# Placa_frizzy.net
KiCad netlist of a schematic drawn in EAGLE
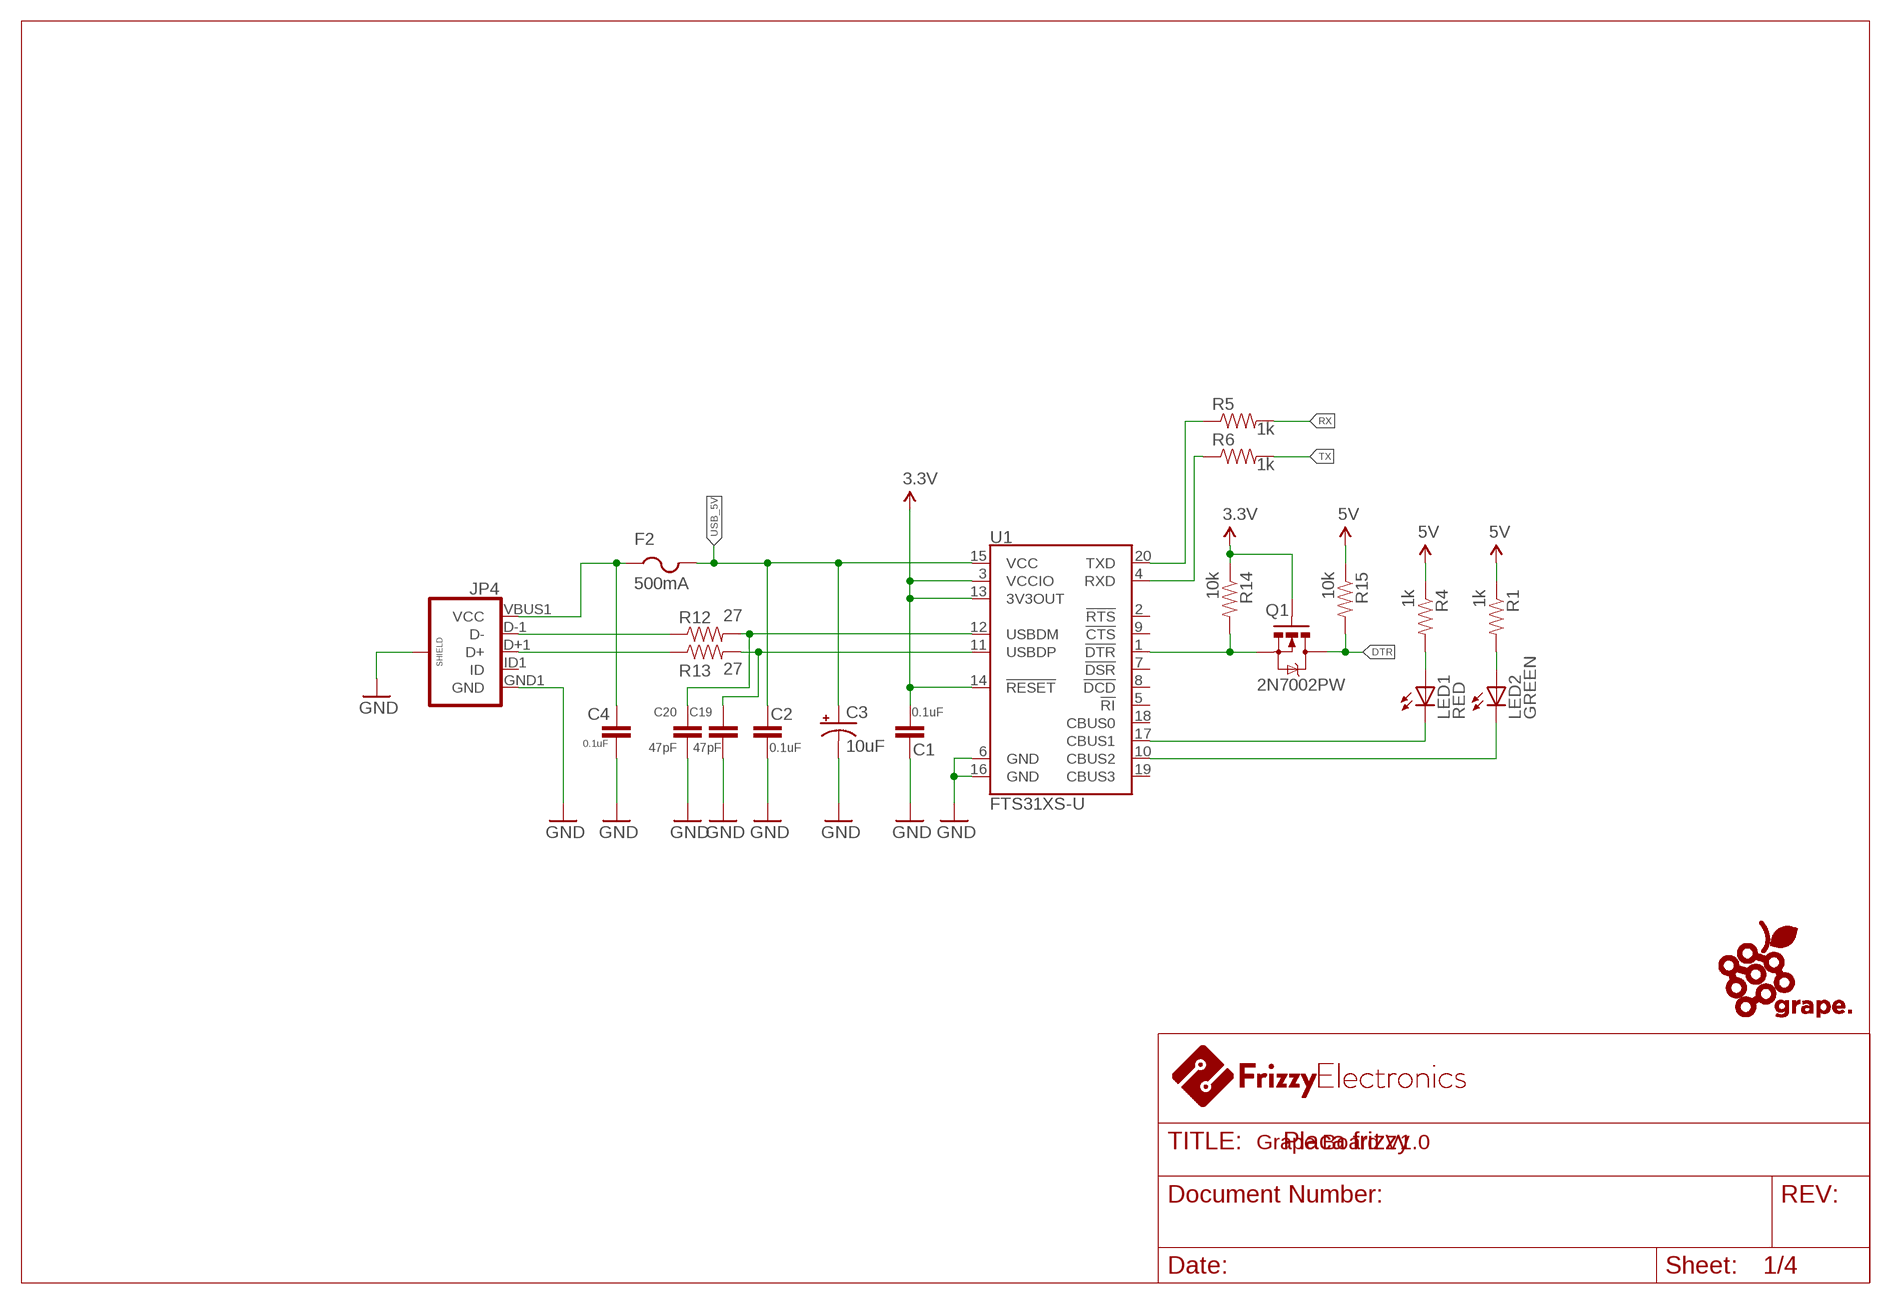
[diagram p0: schematic, sheet 1]
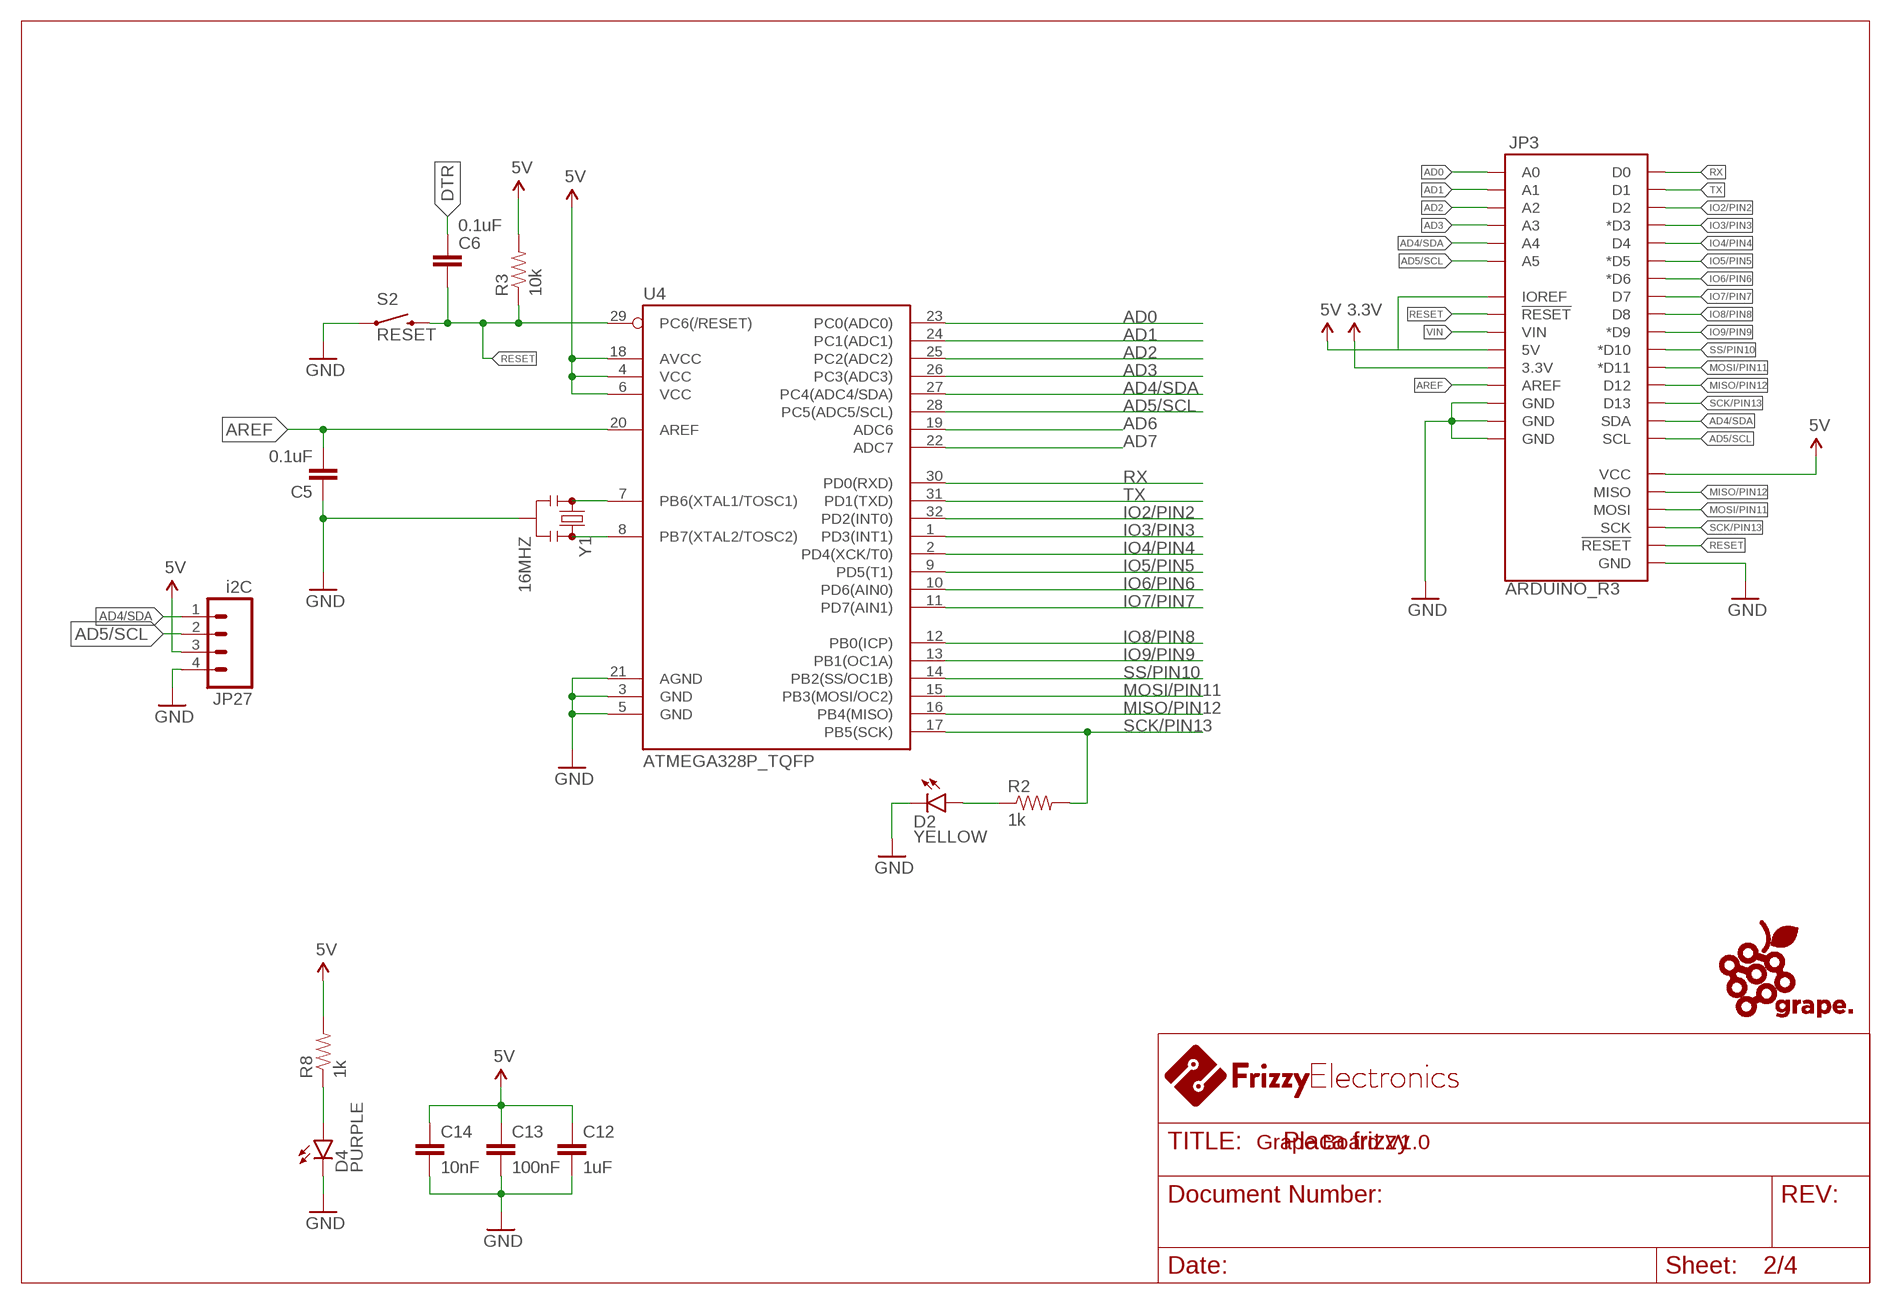
[diagram p1: schematic, sheet 2]
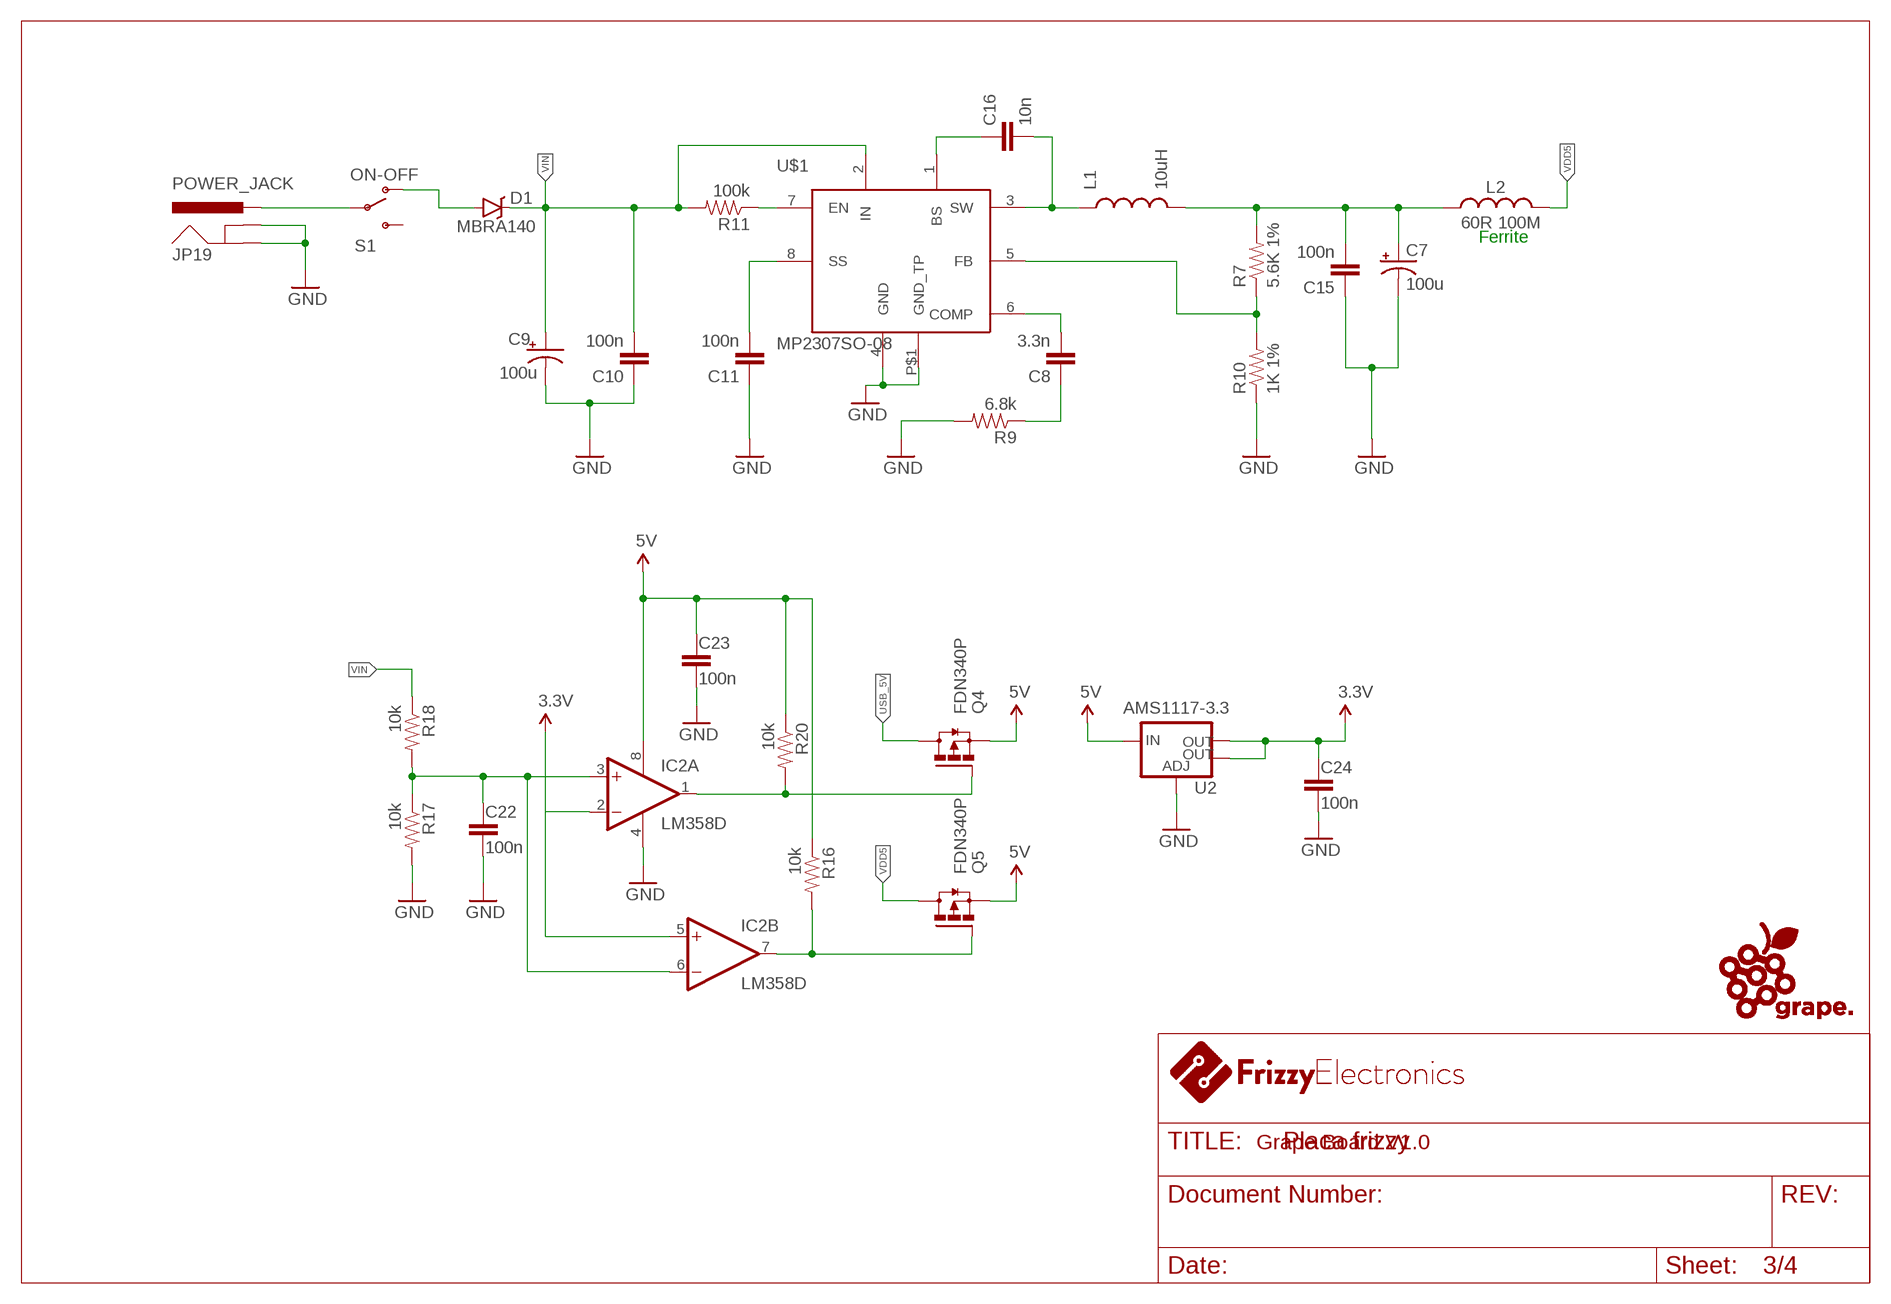
[diagram p2: schematic, sheet 3]
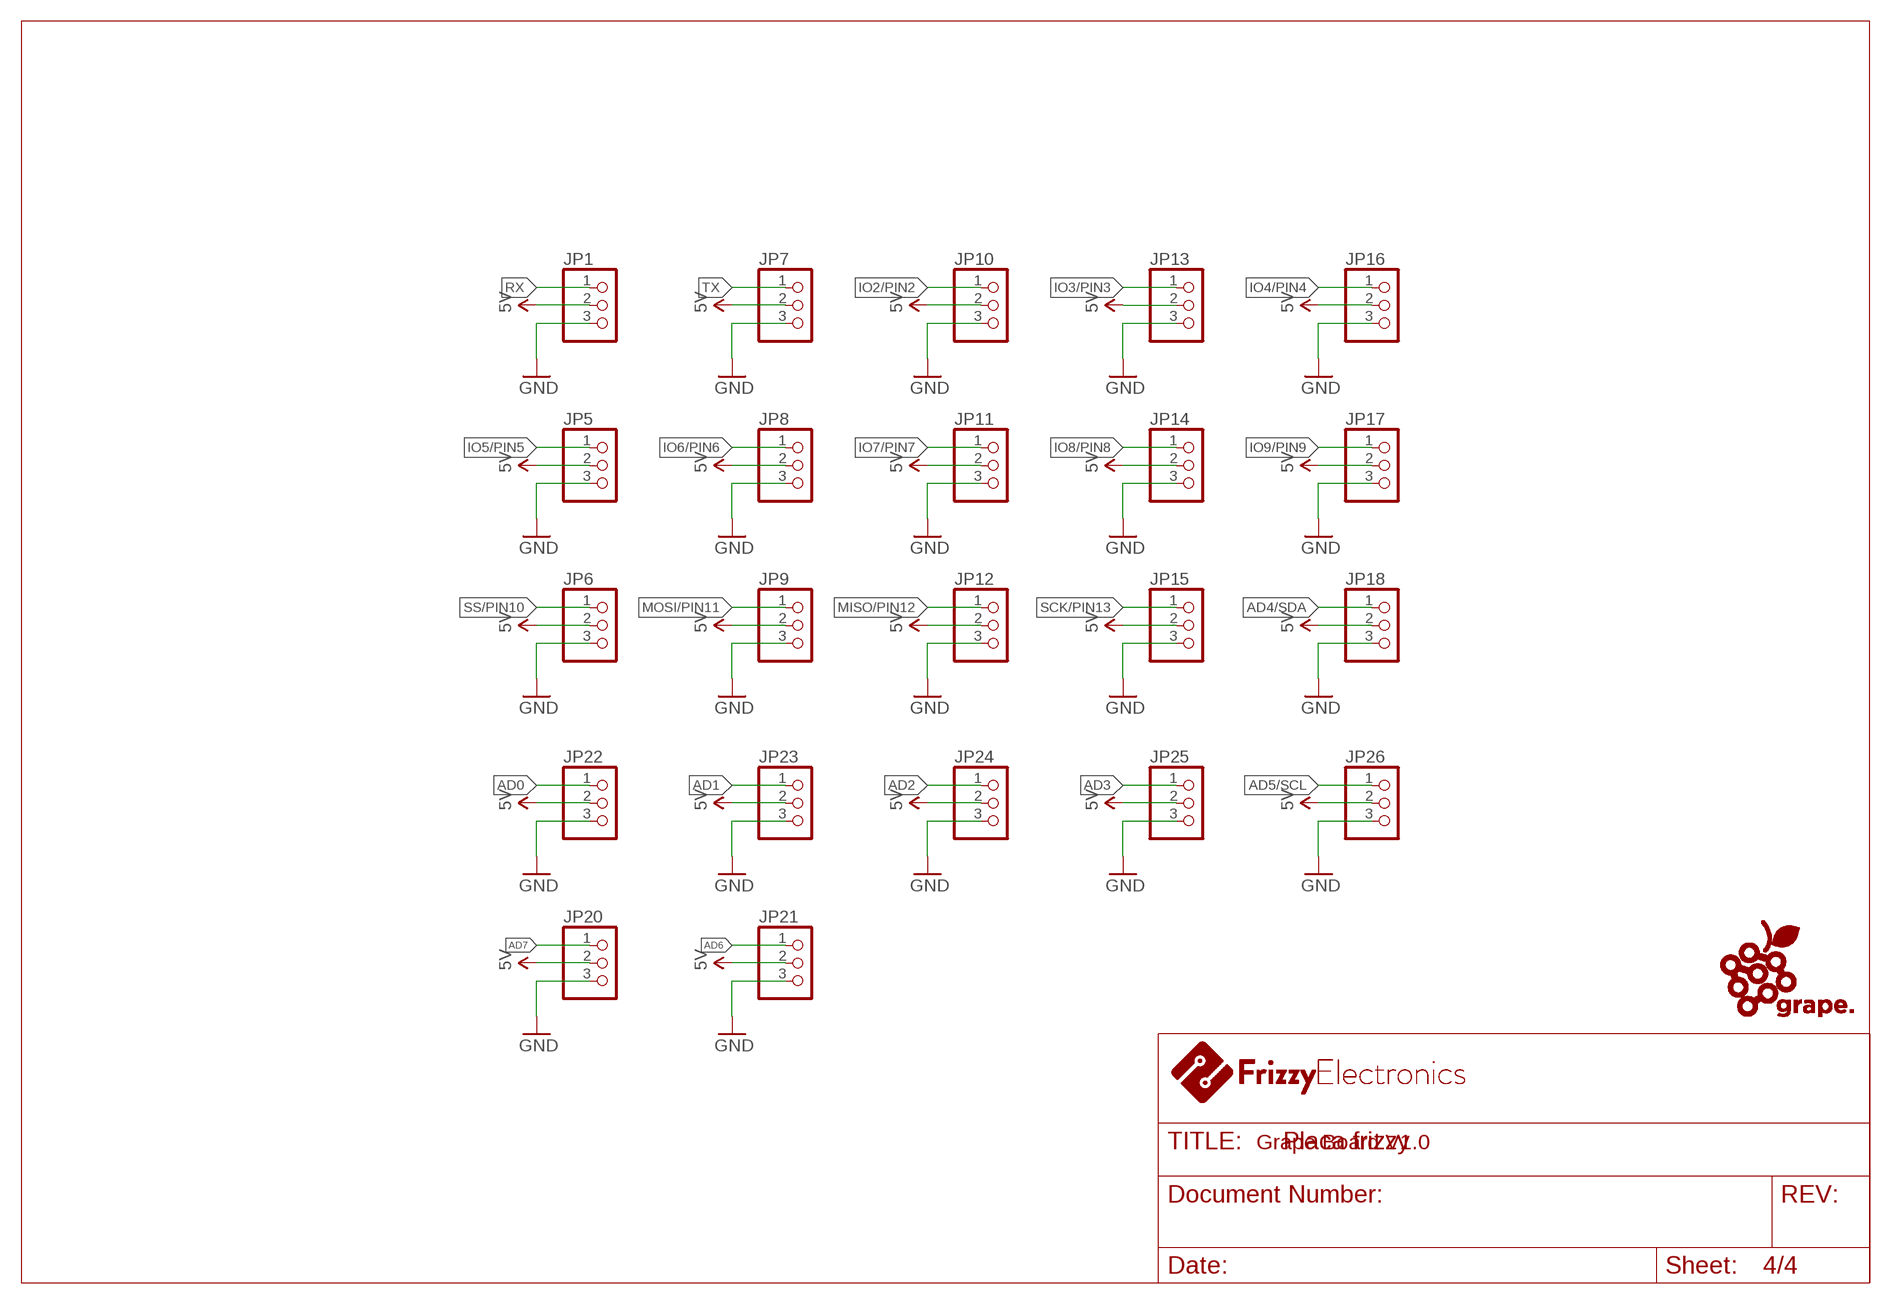
[diagram p3: schematic, sheet 4]

(export (version "E")
  (design (tool "Eeschema 10.0.6"))
  (components
    (comp (ref "JP1")
      (value "PINHD-1X3")
      (footprint "eagle-import:1X03")
      (libsource (lib "eagle-import") (part "PINHD-1X3"))
    )
    (comp (ref "JP5")
      (value "PINHD-1X3")
      (footprint "eagle-import:1X03")
      (libsource (lib "eagle-import") (part "PINHD-1X3"))
    )
    (comp (ref "JP6")
      (value "PINHD-1X3")
      (footprint "eagle-import:1X03")
      (libsource (lib "eagle-import") (part "PINHD-1X3"))
    )
    (comp (ref "JP7")
      (value "PINHD-1X3")
      (footprint "eagle-import:1X03")
      (libsource (lib "eagle-import") (part "PINHD-1X3"))
    )
    (comp (ref "JP8")
      (value "PINHD-1X3")
      (footprint "eagle-import:1X03")
      (libsource (lib "eagle-import") (part "PINHD-1X3"))
    )
    (comp (ref "JP9")
      (value "PINHD-1X3")
      (footprint "eagle-import:1X03")
      (libsource (lib "eagle-import") (part "PINHD-1X3"))
    )
    (comp (ref "JP10")
      (value "PINHD-1X3")
      (footprint "eagle-import:1X03")
      (libsource (lib "eagle-import") (part "PINHD-1X3"))
    )
    (comp (ref "JP11")
      (value "PINHD-1X3")
      (footprint "eagle-import:1X03")
      (libsource (lib "eagle-import") (part "PINHD-1X3"))
    )
    (comp (ref "JP12")
      (value "PINHD-1X3")
      (footprint "eagle-import:1X03")
      (libsource (lib "eagle-import") (part "PINHD-1X3"))
    )
    (comp (ref "JP13")
      (value "PINHD-1X3")
      (footprint "eagle-import:1X03")
      (libsource (lib "eagle-import") (part "PINHD-1X3"))
    )
    (comp (ref "JP14")
      (value "PINHD-1X3")
      (footprint "eagle-import:1X03")
      (libsource (lib "eagle-import") (part "PINHD-1X3"))
    )
    (comp (ref "JP15")
      (value "PINHD-1X3")
      (footprint "eagle-import:1X03")
      (libsource (lib "eagle-import") (part "PINHD-1X3"))
    )
    (comp (ref "JP16")
      (value "PINHD-1X3")
      (footprint "eagle-import:1X03")
      (libsource (lib "eagle-import") (part "PINHD-1X3"))
    )
    (comp (ref "JP17")
      (value "PINHD-1X3")
      (footprint "eagle-import:1X03")
      (libsource (lib "eagle-import") (part "PINHD-1X3"))
    )
    (comp (ref "JP18")
      (value "PINHD-1X3")
      (footprint "eagle-import:1X03")
      (libsource (lib "eagle-import") (part "PINHD-1X3"))
    )
    (comp (ref "JP20")
      (value "PINHD-1X3")
      (footprint "eagle-import:1X03")
      (libsource (lib "eagle-import") (part "PINHD-1X3"))
    )
    (comp (ref "JP21")
      (value "PINHD-1X3")
      (footprint "eagle-import:1X03")
      (libsource (lib "eagle-import") (part "PINHD-1X3"))
    )
    (comp (ref "JP22")
      (value "PINHD-1X3")
      (footprint "eagle-import:1X03")
      (libsource (lib "eagle-import") (part "PINHD-1X3"))
    )
    (comp (ref "JP23")
      (value "PINHD-1X3")
      (footprint "eagle-import:1X03")
      (libsource (lib "eagle-import") (part "PINHD-1X3"))
    )
    (comp (ref "JP24")
      (value "PINHD-1X3")
      (footprint "eagle-import:1X03")
      (libsource (lib "eagle-import") (part "PINHD-1X3"))
    )
    (comp (ref "JP25")
      (value "PINHD-1X3")
      (footprint "eagle-import:1X03")
      (libsource (lib "eagle-import") (part "PINHD-1X3"))
    )
    (comp (ref "JP26")
      (value "PINHD-1X3")
      (footprint "eagle-import:1X03")
      (libsource (lib "eagle-import") (part "PINHD-1X3"))
    )
    (comp (ref "C5")
      (value "0.1uF")
      (footprint "eagle-import:0603-CAP")
      (libsource (lib "eagle-import") (part "CAP0603-CAP"))
    )
    (comp (ref "C6")
      (value "0.1uF")
      (footprint "eagle-import:0603-CAP")
      (libsource (lib "eagle-import") (part "CAP0603-CAP"))
    )
    (comp (ref "C12")
      (value "1uF")
      (footprint "eagle-import:0603-CAP")
      (libsource (lib "eagle-import") (part "CAP0603-CAP"))
    )
    (comp (ref "C13")
      (value "100nF")
      (footprint "eagle-import:0603-CAP")
      (libsource (lib "eagle-import") (part "CAP0603-CAP"))
    )
    (comp (ref "C14")
      (value "10nF")
      (footprint "eagle-import:0603-CAP")
      (libsource (lib "eagle-import") (part "CAP0603-CAP"))
    )
    (comp (ref "D2")
      (value "YELLOW")
      (footprint "eagle-import:LED-0603")
      (libsource (lib "eagle-import") (part "LED-BLUE0603"))
    )
    (comp (ref "D4")
      (value "PURPLE")
      (footprint "eagle-import:LED-0603")
      (libsource (lib "eagle-import") (part "LED0603"))
    )
    (comp (ref "JP3")
      (value "ARDUINO_R3")
      (footprint "eagle-import:ARDUINO_R3")
      (libsource (lib "eagle-import") (part "ARDUINO_R3"))
    )
    (comp (ref "JP27")
      (value "i2C")
      (footprint "eagle-import:JST-4-PTH")
      (libsource (lib "eagle-import") (part "M04JST-PTH"))
    )
    (comp (ref "R2")
      (value "1k")
      (footprint "eagle-import:0805")
      (libsource (lib "eagle-import") (part "RESISTOR0805-RES"))
    )
    (comp (ref "R3")
      (value "10k")
      (footprint "eagle-import:0805")
      (libsource (lib "eagle-import") (part "RESISTOR0805-RES"))
    )
    (comp (ref "R8")
      (value "1k")
      (footprint "eagle-import:0805")
      (libsource (lib "eagle-import") (part "RESISTOR0805-RES"))
    )
    (comp (ref "S2")
      (value "RESET")
      (footprint "eagle-import:TACTILE-PTH-SIDEEZ")
      (libsource (lib "eagle-import") (part "SWITCH-MOMENTARY-2SIDE_EZ"))
    )
    (comp (ref "U4")
      (value "ATMEGA328P_TQFP")
      (footprint "eagle-import:TQFP32-08")
      (libsource (lib "eagle-import") (part "ATMEGA328P_TQFP"))
    )
    (comp (ref "Y1")
      (value "16MHZ")
      (footprint "eagle-import:RESONATOR-SMD")
      (libsource (lib "eagle-import") (part "RESONATOR16MHZ"))
    )
    (comp (ref "C1")
      (value "0.1uF")
      (footprint "eagle-import:0805")
      (libsource (lib "eagle-import") (part "SparkFun-Passives_CAP0805"))
    )
    (comp (ref "C2")
      (value "0.1uF")
      (footprint "eagle-import:0805")
      (libsource (lib "eagle-import") (part "SparkFun-Passives_CAP0805"))
    )
    (comp (ref "C3")
      (value "10uF")
      (footprint "eagle-import:EIA3216")
      (libsource (lib "eagle-import") (part "10UF-16V-10%(TANT)"))
    )
    (comp (ref "C4")
      (value "0.1uF")
      (footprint "eagle-import:0805")
      (libsource (lib "eagle-import") (part "SparkFun-Passives_CAP0805"))
    )
    (comp (ref "C19")
      (value "47pF")
      (footprint "eagle-import:0805")
      (libsource (lib "eagle-import") (part "SparkFun-Passives_CAP0805"))
    )
    (comp (ref "C20")
      (value "47pF")
      (footprint "eagle-import:0805")
      (libsource (lib "eagle-import") (part "SparkFun-Passives_CAP0805"))
    )
    (comp (ref "F2")
      (value "500mA")
      (footprint "eagle-import:1812")
      (libsource (lib "eagle-import") (part "PTCFUSE-1812"))
    )
    (comp (ref "JP4")
      (value "USB_MICROB_PLUGCONN-11752")
      (footprint "eagle-import:USB-B-MICRO-SMD_V03")
      (libsource (lib "eagle-import") (part "USB_MICROB_PLUGCONN-11752"))
    )
    (comp (ref "LED1")
      (value "RED")
      (footprint "eagle-import:CHIP-LED0805")
      (libsource (lib "eagle-import") (part "LEDCHIP-LED0805"))
    )
    (comp (ref "LED2")
      (value "GREEN")
      (footprint "eagle-import:CHIP-LED0805")
      (libsource (lib "eagle-import") (part "LEDCHIP-LED0805"))
    )
    (comp (ref "Q1")
      (value "2N7002PW")
      (footprint "eagle-import:SOT323")
      (libsource (lib "eagle-import") (part "MOSFET-NCHANNEL2N7002PW"))
    )
    (comp (ref "R1")
      (value "1k")
      (footprint "eagle-import:0805")
      (libsource (lib "eagle-import") (part "RESISTOR0805-RES"))
    )
    (comp (ref "R4")
      (value "1k")
      (footprint "eagle-import:0805")
      (libsource (lib "eagle-import") (part "RESISTOR0805-RES"))
    )
    (comp (ref "R5")
      (value "1k")
      (footprint "eagle-import:0805")
      (libsource (lib "eagle-import") (part "RESISTOR0805-RES"))
    )
    (comp (ref "R6")
      (value "1k")
      (footprint "eagle-import:0805")
      (libsource (lib "eagle-import") (part "RESISTOR0805-RES"))
    )
    (comp (ref "R12")
      (value "27")
      (footprint "eagle-import:0805")
      (libsource (lib "eagle-import") (part "RESISTOR0805-RES"))
    )
    (comp (ref "R13")
      (value "27")
      (footprint "eagle-import:0805")
      (libsource (lib "eagle-import") (part "RESISTOR0805-RES"))
    )
    (comp (ref "R14")
      (value "10k")
      (footprint "eagle-import:0805")
      (libsource (lib "eagle-import") (part "RESISTOR0805-RES"))
    )
    (comp (ref "R15")
      (value "10k")
      (footprint "eagle-import:0805")
      (libsource (lib "eagle-import") (part "RESISTOR0805-RES"))
    )
    (comp (ref "U1")
      (value "FTS31XS-U")
      (footprint "eagle-import:SSOP20_L")
      (libsource (lib "eagle-import") (part "FT231XS"))
    )
    (comp (ref "C7")
      (value "100u")
      (footprint "eagle-import:PANASONIC_D")
      (libsource (lib "eagle-import") (part "47UF-50V-20%(ELECT)"))
    )
    (comp (ref "C8")
      (value "3.3n")
      (footprint "eagle-import:0805")
      (libsource (lib "eagle-import") (part "SparkFun-Passives_CAP0805"))
    )
    (comp (ref "C9")
      (value "100u")
      (footprint "eagle-import:PANASONIC_D")
      (libsource (lib "eagle-import") (part "47UF-50V-20%(ELECT)"))
    )
    (comp (ref "C10")
      (value "100n")
      (footprint "eagle-import:0805")
      (libsource (lib "eagle-import") (part "SparkFun-Passives_CAP0805"))
    )
    (comp (ref "C11")
      (value "100n")
      (footprint "eagle-import:0805")
      (libsource (lib "eagle-import") (part "SparkFun-Passives_CAP0805"))
    )
    (comp (ref "C15")
      (value "100n")
      (footprint "eagle-import:0805")
      (libsource (lib "eagle-import") (part "SparkFun-Passives_CAP0805"))
    )
    (comp (ref "C16")
      (value "10n")
      (footprint "eagle-import:0805")
      (libsource (lib "eagle-import") (part "SparkFun-Passives_CAP0805"))
    )
    (comp (ref "C22")
      (value "100n")
      (footprint "eagle-import:0805")
      (libsource (lib "eagle-import") (part "SparkFun-Passives_CAP0805"))
    )
    (comp (ref "C23")
      (value "100n")
      (footprint "eagle-import:0805")
      (libsource (lib "eagle-import") (part "SparkFun-Passives_CAP0805"))
    )
    (comp (ref "C24")
      (value "100n")
      (footprint "eagle-import:0805")
      (libsource (lib "eagle-import") (part "SparkFun-Passives_CAP0805"))
    )
    (comp (ref "D1")
      (value "MBRA140")
      (footprint "eagle-import:SMA-DIODE")
      (libsource (lib "eagle-import") (part "MBRA140"))
    )
    (comp (ref "IC2")
      (value "LM358D")
      (footprint "eagle-import:SO08")
      (libsource (lib "eagle-import") (part "LM358D"))
    )
    (comp (ref "JP19")
      (value "POWER_JACK")
      (footprint "eagle-import:POWER_JACK_PTH")
      (libsource (lib "eagle-import") (part "POWER_JACKPTH"))
    )
    (comp (ref "L1")
      (value "10uH")
      (footprint "eagle-import:NPI75C")
      (libsource (lib "eagle-import") (part "INDUCTORNPI75"))
    )
    (comp (ref "L2")
      (value "60R 100M")
      (footprint "eagle-import:0805")
      (libsource (lib "eagle-import") (part "INDUCTOR0805"))
    )
    (comp (ref "Q4")
      (value "FDN340P")
      (footprint "eagle-import:SUPER-SOT3")
      (libsource (lib "eagle-import") (part "FDN360P"))
    )
    (comp (ref "Q5")
      (value "FDN340P")
      (footprint "eagle-import:SUPER-SOT3")
      (libsource (lib "eagle-import") (part "FDN360P"))
    )
    (comp (ref "R7")
      (value "5.6K 1%")
      (footprint "eagle-import:0805")
      (libsource (lib "eagle-import") (part "RESISTOR0805-RES"))
    )
    (comp (ref "R9")
      (value "6.8k")
      (footprint "eagle-import:0805")
      (libsource (lib "eagle-import") (part "RESISTOR0805-RES"))
    )
    (comp (ref "R10")
      (value "1K 1%")
      (footprint "eagle-import:0805")
      (libsource (lib "eagle-import") (part "RESISTOR0805-RES"))
    )
    (comp (ref "R11")
      (value "100k")
      (footprint "eagle-import:0805")
      (libsource (lib "eagle-import") (part "RESISTOR0805-RES"))
    )
    (comp (ref "R16")
      (value "10k")
      (footprint "eagle-import:0805")
      (libsource (lib "eagle-import") (part "RESISTOR0805-RES"))
    )
    (comp (ref "R17")
      (value "10k")
      (footprint "eagle-import:0805")
      (libsource (lib "eagle-import") (part "RESISTOR0805-RES"))
    )
    (comp (ref "R18")
      (value "10k")
      (footprint "eagle-import:0805")
      (libsource (lib "eagle-import") (part "RESISTOR0805-RES"))
    )
    (comp (ref "R20")
      (value "10k")
      (footprint "eagle-import:0805")
      (libsource (lib "eagle-import") (part "RESISTOR0805-RES"))
    )
    (comp (ref "S1")
      (value "ON-OFF")
      (footprint "eagle-import:SWITCH-SPST-SMD-A")
      (libsource (lib "eagle-import") (part "SWITCH-SPDT-SMD-A"))
    )
    (comp (ref "U$1")
      (value "MP2307SO-08")
      (footprint "eagle-import:SO-08")
      (libsource (lib "eagle-import") (part "MP2307SO-08"))
    )
    (comp (ref "U2")
      (value "AMS1117-3.3")
      (footprint "eagle-import:SOT223")
      (libsource (lib "eagle-import") (part "V_REG_LM1117SOT223"))
    )
  )
  (nets
    (net (code "1") (name "3.3V") (class "Default")
      (node (ref "C1") (pin "2") (pinfunction "2_2") (pintype "passive"))
      (node (ref "C24") (pin "1") (pinfunction "1_1") (pintype "passive"))
      (node (ref "IC2") (pin "2") (pinfunction "-IN_2") (pintype "input"))
      (node (ref "IC2") (pin "5") (pinfunction "+IN_5") (pintype "input"))
      (node (ref "JP3") (pin "3.3V") (pinfunction "3.3V_3.3V") (pintype "bidirectional"))
      (node (ref "Q1") (pin "1") (pinfunction "G_1") (pintype "passive"))
      (node (ref "R14") (pin "1") (pinfunction "1_1") (pintype "passive"))
      (node (ref "U1") (pin "13") (pinfunction "3V3OUT_13") (pintype "bidirectional"))
      (node (ref "U1") (pin "14") (pinfunction "~{RESET}_14") (pintype "bidirectional"))
      (node (ref "U1") (pin "3") (pinfunction "VCCIO_3") (pintype "bidirectional"))
      (node (ref "U2") (pin "2") (pinfunction "OUT_2") (pintype "output"))
      (node (ref "U2") (pin "4") (pinfunction "OUT_4") (pintype "output"))
    )
    (net (code "2") (name "5V") (class "Default")
      (node (ref "C12") (pin "1") (pinfunction "1_1") (pintype "passive"))
      (node (ref "C13") (pin "1") (pinfunction "1_1") (pintype "passive"))
      (node (ref "C14") (pin "1") (pinfunction "1_1") (pintype "passive"))
      (node (ref "C23") (pin "1") (pinfunction "1_1") (pintype "passive"))
      (node (ref "IC2") (pin "8") (pinfunction "V+_8") (pintype "power_in"))
      (node (ref "JP1") (pin "2") (pinfunction "2_2") (pintype "passive"))
      (node (ref "JP10") (pin "2") (pinfunction "2_2") (pintype "passive"))
      (node (ref "JP11") (pin "2") (pinfunction "2_2") (pintype "passive"))
      (node (ref "JP12") (pin "2") (pinfunction "2_2") (pintype "passive"))
      (node (ref "JP13") (pin "2") (pinfunction "2_2") (pintype "passive"))
      (node (ref "JP14") (pin "2") (pinfunction "2_2") (pintype "passive"))
      (node (ref "JP15") (pin "2") (pinfunction "2_2") (pintype "passive"))
      (node (ref "JP16") (pin "2") (pinfunction "2_2") (pintype "passive"))
      (node (ref "JP17") (pin "2") (pinfunction "2_2") (pintype "passive"))
      (node (ref "JP18") (pin "2") (pinfunction "2_2") (pintype "passive"))
      (node (ref "JP20") (pin "2") (pinfunction "2_2") (pintype "passive"))
      (node (ref "JP21") (pin "2") (pinfunction "2_2") (pintype "passive"))
      (node (ref "JP22") (pin "2") (pinfunction "2_2") (pintype "passive"))
      (node (ref "JP23") (pin "2") (pinfunction "2_2") (pintype "passive"))
      (node (ref "JP24") (pin "2") (pinfunction "2_2") (pintype "passive"))
      (node (ref "JP25") (pin "2") (pinfunction "2_2") (pintype "passive"))
      (node (ref "JP26") (pin "2") (pinfunction "2_2") (pintype "passive"))
      (node (ref "JP27") (pin "3") (pinfunction "3_3") (pintype "passive"))
      (node (ref "JP3") (pin "5V") (pinfunction "5V_5V") (pintype "bidirectional"))
      (node (ref "JP3") (pin "IOREF") (pinfunction "IOREF_IOREF") (pintype "bidirectional"))
      (node (ref "JP3") (pin "VCC") (pinfunction "VCC_VCC") (pintype "bidirectional"))
      (node (ref "JP5") (pin "2") (pinfunction "2_2") (pintype "passive"))
      (node (ref "JP6") (pin "2") (pinfunction "2_2") (pintype "passive"))
      (node (ref "JP7") (pin "2") (pinfunction "2_2") (pintype "passive"))
      (node (ref "JP8") (pin "2") (pinfunction "2_2") (pintype "passive"))
      (node (ref "JP9") (pin "2") (pinfunction "2_2") (pintype "passive"))
      (node (ref "Q4") (pin "2") (pinfunction "S_2") (pintype "passive"))
      (node (ref "Q5") (pin "2") (pinfunction "S_2") (pintype "passive"))
      (node (ref "R1") (pin "1") (pinfunction "1_1") (pintype "passive"))
      (node (ref "R15") (pin "1") (pinfunction "1_1") (pintype "passive"))
      (node (ref "R16") (pin "1") (pinfunction "1_1") (pintype "passive"))
      (node (ref "R20") (pin "1") (pinfunction "1_1") (pintype "passive"))
      (node (ref "R3") (pin "2") (pinfunction "2_2") (pintype "passive"))
      (node (ref "R4") (pin "1") (pinfunction "1_1") (pintype "passive"))
      (node (ref "R8") (pin "2") (pinfunction "2_2") (pintype "passive"))
      (node (ref "U2") (pin "3") (pinfunction "IN_3") (pintype "input"))
      (node (ref "U4") (pin "18") (pinfunction "AVCC_18") (pintype "bidirectional"))
      (node (ref "U4") (pin "4") (pinfunction "VCC_4") (pintype "bidirectional"))
      (node (ref "U4") (pin "6") (pinfunction "VCC_6") (pintype "bidirectional"))
    )
    (net (code "3") (name "AD0") (class "Default")
      (node (ref "JP22") (pin "1") (pinfunction "1_1") (pintype "passive"))
      (node (ref "JP3") (pin "A0") (pinfunction "A0_A0") (pintype "bidirectional"))
      (node (ref "U4") (pin "23") (pinfunction "PC0(ADC0)_23") (pintype "bidirectional"))
    )
    (net (code "4") (name "AD1") (class "Default")
      (node (ref "JP23") (pin "1") (pinfunction "1_1") (pintype "passive"))
      (node (ref "JP3") (pin "A1") (pinfunction "A1_A1") (pintype "bidirectional"))
      (node (ref "U4") (pin "24") (pinfunction "PC1(ADC1)_24") (pintype "bidirectional"))
    )
    (net (code "5") (name "AD2") (class "Default")
      (node (ref "JP24") (pin "1") (pinfunction "1_1") (pintype "passive"))
      (node (ref "JP3") (pin "A2") (pinfunction "A2_A2") (pintype "bidirectional"))
      (node (ref "U4") (pin "25") (pinfunction "PC2(ADC2)_25") (pintype "bidirectional"))
    )
    (net (code "6") (name "AD3") (class "Default")
      (node (ref "JP25") (pin "1") (pinfunction "1_1") (pintype "passive"))
      (node (ref "JP3") (pin "A3") (pinfunction "A3_A3") (pintype "bidirectional"))
      (node (ref "U4") (pin "26") (pinfunction "PC3(ADC3)_26") (pintype "bidirectional"))
    )
    (net (code "7") (name "AD4{slash}SDA") (class "Default")
      (node (ref "JP18") (pin "1") (pinfunction "1_1") (pintype "passive"))
      (node (ref "JP27") (pin "1") (pinfunction "1_1") (pintype "passive"))
      (node (ref "JP3") (pin "A4") (pinfunction "A4_A4") (pintype "bidirectional"))
      (node (ref "JP3") (pin "SDA") (pinfunction "SDA_SDA") (pintype "bidirectional"))
      (node (ref "U4") (pin "27") (pinfunction "PC4(ADC4/SDA)_27") (pintype "bidirectional"))
    )
    (net (code "8") (name "AD5{slash}SCL") (class "Default")
      (node (ref "JP26") (pin "1") (pinfunction "1_1") (pintype "passive"))
      (node (ref "JP27") (pin "2") (pinfunction "2_2") (pintype "passive"))
      (node (ref "JP3") (pin "A5") (pinfunction "A5_A5") (pintype "bidirectional"))
      (node (ref "JP3") (pin "SCL") (pinfunction "SCL_SCL") (pintype "bidirectional"))
      (node (ref "U4") (pin "28") (pinfunction "PC5(ADC5/SCL)_28") (pintype "bidirectional"))
    )
    (net (code "9") (name "AD6") (class "Default")
      (node (ref "JP21") (pin "1") (pinfunction "1_1") (pintype "passive"))
      (node (ref "U4") (pin "19") (pinfunction "ADC6_19") (pintype "bidirectional"))
    )
    (net (code "10") (name "AD7") (class "Default")
      (node (ref "JP20") (pin "1") (pinfunction "1_1") (pintype "passive"))
      (node (ref "U4") (pin "22") (pinfunction "ADC7_22") (pintype "bidirectional"))
    )
    (net (code "11") (name "AREF") (class "Default")
      (node (ref "C5") (pin "2") (pinfunction "2_2") (pintype "passive"))
      (node (ref "JP3") (pin "AREF") (pinfunction "AREF_AREF") (pintype "bidirectional"))
      (node (ref "U4") (pin "20") (pinfunction "AREF_20") (pintype "bidirectional"))
    )
    (net (code "12") (name "DTR") (class "Default")
      (node (ref "C6") (pin "1") (pinfunction "1_1") (pintype "passive"))
      (node (ref "Q1") (pin "3") (pinfunction "D_3") (pintype "passive"))
      (node (ref "R15") (pin "2") (pinfunction "2_2") (pintype "passive"))
    )
    (net (code "13") (name "GND") (class "Default")
      (node (ref "C1") (pin "1") (pinfunction "1_1") (pintype "passive"))
      (node (ref "C10") (pin "1") (pinfunction "1_1") (pintype "passive"))
      (node (ref "C11") (pin "1") (pinfunction "1_1") (pintype "passive"))
      (node (ref "C12") (pin "2") (pinfunction "2_2") (pintype "passive"))
      (node (ref "C13") (pin "2") (pinfunction "2_2") (pintype "passive"))
      (node (ref "C14") (pin "2") (pinfunction "2_2") (pintype "passive"))
      (node (ref "C15") (pin "1") (pinfunction "1_1") (pintype "passive"))
      (node (ref "C19") (pin "1") (pinfunction "1_1") (pintype "passive"))
      (node (ref "C2") (pin "1") (pinfunction "1_1") (pintype "passive"))
      (node (ref "C20") (pin "1") (pinfunction "1_1") (pintype "passive"))
      (node (ref "C22") (pin "2") (pinfunction "2_2") (pintype "passive"))
      (node (ref "C23") (pin "2") (pinfunction "2_2") (pintype "passive"))
      (node (ref "C24") (pin "2") (pinfunction "2_2") (pintype "passive"))
      (node (ref "C3") (pin "C") (pinfunction "-_C") (pintype "passive"))
      (node (ref "C4") (pin "2") (pinfunction "2_2") (pintype "passive"))
      (node (ref "C5") (pin "1") (pinfunction "1_1") (pintype "passive"))
      (node (ref "C7") (pin "-") (pinfunction "-_-") (pintype "passive"))
      (node (ref "C9") (pin "-") (pinfunction "-_-") (pintype "passive"))
      (node (ref "D2") (pin "C") (pinfunction "C_C") (pintype "passive"))
      (node (ref "D4") (pin "C") (pinfunction "C_C") (pintype "passive"))
      (node (ref "IC2") (pin "4") (pinfunction "V-_4") (pintype "power_in"))
      (node (ref "JP1") (pin "3") (pinfunction "3_3") (pintype "passive"))
      (node (ref "JP10") (pin "3") (pinfunction "3_3") (pintype "passive"))
      (node (ref "JP11") (pin "3") (pinfunction "3_3") (pintype "passive"))
      (node (ref "JP12") (pin "3") (pinfunction "3_3") (pintype "passive"))
      (node (ref "JP13") (pin "3") (pinfunction "3_3") (pintype "passive"))
      (node (ref "JP14") (pin "3") (pinfunction "3_3") (pintype "passive"))
      (node (ref "JP15") (pin "3") (pinfunction "3_3") (pintype "passive"))
      (node (ref "JP16") (pin "3") (pinfunction "3_3") (pintype "passive"))
      (node (ref "JP17") (pin "3") (pinfunction "3_3") (pintype "passive"))
      (node (ref "JP18") (pin "3") (pinfunction "3_3") (pintype "passive"))
      (node (ref "JP19") (pin "GND") (pinfunction "GND_GND") (pintype "bidirectional"))
      (node (ref "JP19") (pin "GNDBREAK") (pinfunction "GNDBREAK_GNDBREAK") (pintype "bidirectional"))
      (node (ref "JP20") (pin "3") (pinfunction "3_3") (pintype "passive"))
      (node (ref "JP21") (pin "3") (pinfunction "3_3") (pintype "passive"))
      (node (ref "JP22") (pin "3") (pinfunction "3_3") (pintype "passive"))
      (node (ref "JP23") (pin "3") (pinfunction "3_3") (pintype "passive"))
      (node (ref "JP24") (pin "3") (pinfunction "3_3") (pintype "passive"))
      (node (ref "JP25") (pin "3") (pinfunction "3_3") (pintype "passive"))
      (node (ref "JP26") (pin "3") (pinfunction "3_3") (pintype "passive"))
      (node (ref "JP27") (pin "4") (pinfunction "4_4") (pintype "passive"))
      (node (ref "JP3") (pin "GND@1") (pinfunction "GND_GND@1") (pintype "bidirectional"))
      (node (ref "JP3") (pin "GND@2") (pinfunction "GND_GND@2") (pintype "bidirectional"))
      (node (ref "JP3") (pin "GND@3") (pinfunction "GND_GND@3") (pintype "bidirectional"))
      (node (ref "JP3") (pin "GND@4") (pinfunction "GND_GND@4") (pintype "bidirectional"))
      (node (ref "JP4") (pin "GND1") (pinfunction "GND_GND1") (pintype "bidirectional"))
      (node (ref "JP4") (pin "SHIELD1") (pinfunction "SHIELD_SHIELD1") (pintype "bidirectional"))
      (node (ref "JP4") (pin "SHIELD2") (pinfunction "SHIELD_SHIELD2") (pintype "bidirectional"))
      (node (ref "JP4") (pin "SHIELD3") (pinfunction "SHIELD_SHIELD3") (pintype "bidirectional"))
      (node (ref "JP5") (pin "3") (pinfunction "3_3") (pintype "passive"))
      (node (ref "JP6") (pin "3") (pinfunction "3_3") (pintype "passive"))
      (node (ref "JP7") (pin "3") (pinfunction "3_3") (pintype "passive"))
      (node (ref "JP8") (pin "3") (pinfunction "3_3") (pintype "passive"))
      (node (ref "JP9") (pin "3") (pinfunction "3_3") (pintype "passive"))
      (node (ref "R10") (pin "1") (pinfunction "1_1") (pintype "passive"))
      (node (ref "R17") (pin "2") (pinfunction "2_2") (pintype "passive"))
      (node (ref "R9") (pin "2") (pinfunction "2_2") (pintype "passive"))
      (node (ref "S2") (pin "1") (pinfunction "1_1") (pintype "passive"))
      (node (ref "U$1") (pin "4") (pinfunction "GND_4") (pintype "bidirectional"))
      (node (ref "U$1") (pin "P$1") (pinfunction "GND_TP_P$1") (pintype "bidirectional"))
      (node (ref "U1") (pin "16") (pinfunction "GND_16") (pintype "bidirectional"))
      (node (ref "U1") (pin "6") (pinfunction "GND_6") (pintype "bidirectional"))
      (node (ref "U2") (pin "1") (pinfunction "ADJ_1") (pintype "input"))
      (node (ref "U4") (pin "21") (pinfunction "AGND_21") (pintype "bidirectional"))
      (node (ref "U4") (pin "3") (pinfunction "GND_3") (pintype "bidirectional"))
      (node (ref "U4") (pin "5") (pinfunction "GND_5") (pintype "bidirectional"))
      (node (ref "Y1") (pin "2") (pinfunction "2_2") (pintype "passive"))
    )
    (net (code "14") (name "IO2{slash}PIN2") (class "Default")
      (node (ref "JP10") (pin "1") (pinfunction "1_1") (pintype "passive"))
      (node (ref "JP3") (pin "D2") (pinfunction "D2_D2") (pintype "bidirectional"))
      (node (ref "U4") (pin "32") (pinfunction "PD2(INT0)_32") (pintype "bidirectional"))
    )
    (net (code "15") (name "IO3{slash}PIN3") (class "Default")
      (node (ref "JP13") (pin "1") (pinfunction "1_1") (pintype "passive"))
      (node (ref "JP3") (pin "D3") (pinfunction "*D3_D3") (pintype "bidirectional"))
      (node (ref "U4") (pin "1") (pinfunction "PD3(INT1)_1") (pintype "bidirectional"))
    )
    (net (code "16") (name "IO4{slash}PIN4") (class "Default")
      (node (ref "JP16") (pin "1") (pinfunction "1_1") (pintype "passive"))
      (node (ref "JP3") (pin "D4") (pinfunction "D4_D4") (pintype "bidirectional"))
      (node (ref "U4") (pin "2") (pinfunction "PD4(XCK/T0)_2") (pintype "bidirectional"))
    )
    (net (code "17") (name "IO5{slash}PIN5") (class "Default")
      (node (ref "JP3") (pin "D5") (pinfunction "*D5_D5") (pintype "bidirectional"))
      (node (ref "JP5") (pin "1") (pinfunction "1_1") (pintype "passive"))
      (node (ref "U4") (pin "9") (pinfunction "PD5(T1)_9") (pintype "bidirectional"))
    )
    (net (code "18") (name "IO6{slash}PIN6") (class "Default")
      (node (ref "JP3") (pin "D6") (pinfunction "*D6_D6") (pintype "bidirectional"))
      (node (ref "JP8") (pin "1") (pinfunction "1_1") (pintype "passive"))
      (node (ref "U4") (pin "10") (pinfunction "PD6(AIN0)_10") (pintype "bidirectional"))
    )
    (net (code "19") (name "IO7{slash}PIN7") (class "Default")
      (node (ref "JP11") (pin "1") (pinfunction "1_1") (pintype "passive"))
      (node (ref "JP3") (pin "D7") (pinfunction "D7_D7") (pintype "bidirectional"))
      (node (ref "U4") (pin "11") (pinfunction "PD7(AIN1)_11") (pintype "bidirectional"))
    )
    (net (code "20") (name "IO8{slash}PIN8") (class "Default")
      (node (ref "JP14") (pin "1") (pinfunction "1_1") (pintype "passive"))
      (node (ref "JP3") (pin "D8") (pinfunction "D8_D8") (pintype "bidirectional"))
      (node (ref "U4") (pin "12") (pinfunction "PB0(ICP)_12") (pintype "bidirectional"))
    )
    (net (code "21") (name "IO9{slash}PIN9") (class "Default")
      (node (ref "JP17") (pin "1") (pinfunction "1_1") (pintype "passive"))
      (node (ref "JP3") (pin "D9") (pinfunction "*D9_D9") (pintype "bidirectional"))
      (node (ref "U4") (pin "13") (pinfunction "PB1(OC1A)_13") (pintype "bidirectional"))
    )
    (net (code "22") (name "MISO{slash}PIN12") (class "Default")
      (node (ref "JP12") (pin "1") (pinfunction "1_1") (pintype "passive"))
      (node (ref "JP3") (pin "D12") (pinfunction "D12_D12") (pintype "bidirectional"))
      (node (ref "JP3") (pin "MISO") (pinfunction "MISO_MISO") (pintype "bidirectional"))
      (node (ref "U4") (pin "16") (pinfunction "PB4(MISO)_16") (pintype "bidirectional"))
    )
    (net (code "23") (name "MOSI{slash}PIN11") (class "Default")
      (node (ref "JP3") (pin "D11") (pinfunction "*D11_D11") (pintype "bidirectional"))
      (node (ref "JP3") (pin "MOSI") (pinfunction "MOSI_MOSI") (pintype "bidirectional"))
      (node (ref "JP9") (pin "1") (pinfunction "1_1") (pintype "passive"))
      (node (ref "U4") (pin "15") (pinfunction "PB3(MOSI/OC2)_15") (pintype "bidirectional"))
    )
    (net (code "24") (name "Net-(C8-Pad1)") (class "Default")
      (node (ref "C8") (pin "1") (pinfunction "1_1") (pintype "passive"))
      (node (ref "R9") (pin "1") (pinfunction "1_1") (pintype "passive"))
    )
    (net (code "25") (name "Net-(C15-Pad2)") (class "Default")
      (node (ref "C15") (pin "2") (pinfunction "2_2") (pintype "passive"))
      (node (ref "C7") (pin "+") (pinfunction "+_+") (pintype "passive"))
      (node (ref "L1") (pin "2") (pinfunction "2_2") (pintype "passive"))
      (node (ref "L2") (pin "1") (pinfunction "1_1") (pintype "passive"))
      (node (ref "R7") (pin "2") (pinfunction "2_2") (pintype "passive"))
    )
    (net (code "26") (name "Net-(D2-PadA)") (class "Default")
      (node (ref "D2") (pin "A") (pinfunction "A_A") (pintype "passive"))
      (node (ref "R2") (pin "1") (pinfunction "1_1") (pintype "passive"))
    )
    (net (code "27") (name "Net-(D4-PadA)") (class "Default")
      (node (ref "D4") (pin "A") (pinfunction "A_A") (pintype "passive"))
      (node (ref "R8") (pin "1") (pinfunction "1_1") (pintype "passive"))
    )
    (net (code "28") (name "Net-(IC2A-+IN)") (class "Default")
      (node (ref "C22") (pin "1") (pinfunction "1_1") (pintype "passive"))
      (node (ref "IC2") (pin "3") (pinfunction "+IN_3") (pintype "input"))
      (node (ref "IC2") (pin "6") (pinfunction "-IN_6") (pintype "input"))
      (node (ref "R17") (pin "1") (pinfunction "1_1") (pintype "passive"))
      (node (ref "R18") (pin "2") (pinfunction "2_2") (pintype "passive"))
    )
    (net (code "29") (name "Net-(IC2A-OUT)") (class "Default")
      (node (ref "IC2") (pin "1") (pinfunction "OUT_1") (pintype "output"))
      (node (ref "Q4") (pin "1") (pinfunction "G_1") (pintype "passive"))
      (node (ref "R20") (pin "2") (pinfunction "2_2") (pintype "passive"))
    )
    (net (code "30") (name "Net-(IC2B-OUT)") (class "Default")
      (node (ref "IC2") (pin "7") (pinfunction "OUT_7") (pintype "output"))
      (node (ref "Q5") (pin "1") (pinfunction "G_1") (pintype "passive"))
      (node (ref "R16") (pin "2") (pinfunction "2_2") (pintype "passive"))
    )
    (net (code "31") (name "Net-(JP4-D+)") (class "Default")
      (node (ref "JP4") (pin "D+1") (pinfunction "D+_D+1") (pintype "bidirectional"))
      (node (ref "R13") (pin "1") (pinfunction "1_1") (pintype "passive"))
    )
    (net (code "32") (name "Net-(JP4-D-)") (class "Default")
      (node (ref "JP4") (pin "D-1") (pinfunction "D-_D-1") (pintype "bidirectional"))
      (node (ref "R12") (pin "1") (pinfunction "1_1") (pintype "passive"))
    )
    (net (code "33") (name "Net-(JP4-VCC)") (class "Default")
      (node (ref "C4") (pin "1") (pinfunction "1_1") (pintype "passive"))
      (node (ref "F2") (pin "1") (pinfunction "1_1") (pintype "passive"))
      (node (ref "JP4") (pin "VBUS1") (pinfunction "VCC_VBUS1") (pintype "bidirectional"))
    )
    (net (code "34") (name "Net-(LED1-PadA)") (class "Default")
      (node (ref "LED1") (pin "A") (pinfunction "A_A") (pintype "passive"))
      (node (ref "R4") (pin "2") (pinfunction "2_2") (pintype "passive"))
    )
    (net (code "35") (name "Net-(LED2-PadA)") (class "Default")
      (node (ref "LED2") (pin "A") (pinfunction "A_A") (pintype "passive"))
      (node (ref "R1") (pin "2") (pinfunction "2_2") (pintype "passive"))
    )
    (net (code "36") (name "Net-(Q1-S)") (class "Default")
      (node (ref "Q1") (pin "2") (pinfunction "S_2") (pintype "passive"))
      (node (ref "R14") (pin "2") (pinfunction "2_2") (pintype "passive"))
      (node (ref "U1") (pin "1") (pinfunction "~{DTR}_1") (pintype "bidirectional"))
    )
    (net (code "37") (name "Net-(S1-O)") (class "Default")
      (node (ref "D1") (pin "A") (pinfunction "A_A") (pintype "passive"))
      (node (ref "S1") (pin "1") (pinfunction "O_1") (pintype "passive"))
    )
    (net (code "38") (name "Net-(S1-P)") (class "Default")
      (node (ref "JP19") (pin "PWR") (pinfunction "PWR_PWR") (pintype "bidirectional"))
      (node (ref "S1") (pin "2") (pinfunction "P_2") (pintype "passive"))
    )
    (net (code "39") (name "Net-(U$1-BS)") (class "Default")
      (node (ref "C16") (pin "1") (pinfunction "1_1") (pintype "passive"))
      (node (ref "U$1") (pin "1") (pinfunction "BS_1") (pintype "bidirectional"))
    )
    (net (code "40") (name "Net-(U$1-COMP)") (class "Default")
      (node (ref "C8") (pin "2") (pinfunction "2_2") (pintype "passive"))
      (node (ref "U$1") (pin "6") (pinfunction "COMP_6") (pintype "bidirectional"))
    )
    (net (code "41") (name "Net-(U$1-EN)") (class "Default")
      (node (ref "R11") (pin "1") (pinfunction "1_1") (pintype "passive"))
      (node (ref "U$1") (pin "7") (pinfunction "EN_7") (pintype "bidirectional"))
    )
    (net (code "42") (name "Net-(U$1-FB)") (class "Default")
      (node (ref "R10") (pin "2") (pinfunction "2_2") (pintype "passive"))
      (node (ref "R7") (pin "1") (pinfunction "1_1") (pintype "passive"))
      (node (ref "U$1") (pin "5") (pinfunction "FB_5") (pintype "bidirectional"))
    )
    (net (code "43") (name "Net-(U$1-SS)") (class "Default")
      (node (ref "C11") (pin "2") (pinfunction "2_2") (pintype "passive"))
      (node (ref "U$1") (pin "8") (pinfunction "SS_8") (pintype "bidirectional"))
    )
    (net (code "44") (name "Net-(U$1-SW)") (class "Default")
      (node (ref "C16") (pin "2") (pinfunction "2_2") (pintype "passive"))
      (node (ref "L1") (pin "1") (pinfunction "1_1") (pintype "passive"))
      (node (ref "U$1") (pin "3") (pinfunction "SW_3") (pintype "bidirectional"))
    )
    (net (code "45") (name "Net-(U1-CBUS1)") (class "Default")
      (node (ref "LED1") (pin "C") (pinfunction "C_C") (pintype "passive"))
      (node (ref "U1") (pin "17") (pinfunction "CBUS1_17") (pintype "bidirectional"))
    )
    (net (code "46") (name "Net-(U1-CBUS2)") (class "Default")
      (node (ref "LED2") (pin "C") (pinfunction "C_C") (pintype "passive"))
      (node (ref "U1") (pin "10") (pinfunction "CBUS2_10") (pintype "bidirectional"))
    )
    (net (code "47") (name "Net-(U1-RXD)") (class "Default")
      (node (ref "R6") (pin "1") (pinfunction "1_1") (pintype "passive"))
      (node (ref "U1") (pin "4") (pinfunction "RXD_4") (pintype "bidirectional"))
    )
    (net (code "48") (name "Net-(U1-TXD)") (class "Default")
      (node (ref "R5") (pin "1") (pinfunction "1_1") (pintype "passive"))
      (node (ref "U1") (pin "20") (pinfunction "TXD_20") (pintype "bidirectional"))
    )
    (net (code "49") (name "Net-(U1-USBDM)") (class "Default")
      (node (ref "C20") (pin "2") (pinfunction "2_2") (pintype "passive"))
      (node (ref "R12") (pin "2") (pinfunction "2_2") (pintype "passive"))
      (node (ref "U1") (pin "12") (pinfunction "USBDM_12") (pintype "bidirectional"))
    )
    (net (code "50") (name "Net-(U1-USBDP)") (class "Default")
      (node (ref "C19") (pin "2") (pinfunction "2_2") (pintype "passive"))
      (node (ref "R13") (pin "2") (pinfunction "2_2") (pintype "passive"))
      (node (ref "U1") (pin "11") (pinfunction "USBDP_11") (pintype "bidirectional"))
    )
    (net (code "51") (name "Net-(U4-PB6(XTAL1{slash}TOSC1))") (class "Default")
      (node (ref "U4") (pin "7") (pinfunction "PB6(XTAL1/TOSC1)_7") (pintype "bidirectional"))
      (node (ref "Y1") (pin "1") (pinfunction "1_1") (pintype "passive"))
    )
    (net (code "52") (name "Net-(U4-PB7(XTAL2{slash}TOSC2))") (class "Default")
      (node (ref "U4") (pin "8") (pinfunction "PB7(XTAL2/TOSC2)_8") (pintype "bidirectional"))
      (node (ref "Y1") (pin "3") (pinfunction "3_3") (pintype "passive"))
    )
    (net (code "53") (name "RESET") (class "Default")
      (node (ref "C6") (pin "2") (pinfunction "2_2") (pintype "passive"))
      (node (ref "JP3") (pin "RESET@1") (pinfunction "~{RESET}_RESET@1") (pintype "bidirectional"))
      (node (ref "JP3") (pin "RESET@2") (pinfunction "~{RESET}_RESET@2") (pintype "bidirectional"))
      (node (ref "R3") (pin "1") (pinfunction "1_1") (pintype "passive"))
      (node (ref "S2") (pin "2") (pinfunction "2_2") (pintype "passive"))
      (node (ref "U4") (pin "29") (pinfunction "PC6(/RESET)_29") (pintype "bidirectional"))
    )
    (net (code "54") (name "RX") (class "Default")
      (node (ref "JP1") (pin "1") (pinfunction "1_1") (pintype "passive"))
      (node (ref "JP3") (pin "D0") (pinfunction "D0_D0") (pintype "bidirectional"))
      (node (ref "R5") (pin "2") (pinfunction "2_2") (pintype "passive"))
      (node (ref "U4") (pin "30") (pinfunction "PD0(RXD)_30") (pintype "bidirectional"))
    )
    (net (code "55") (name "SCK{slash}PIN13") (class "Default")
      (node (ref "JP15") (pin "1") (pinfunction "1_1") (pintype "passive"))
      (node (ref "JP3") (pin "D13") (pinfunction "D13_D13") (pintype "bidirectional"))
      (node (ref "JP3") (pin "SCK") (pinfunction "SCK_SCK") (pintype "bidirectional"))
      (node (ref "R2") (pin "2") (pinfunction "2_2") (pintype "passive"))
      (node (ref "U4") (pin "17") (pinfunction "PB5(SCK)_17") (pintype "bidirectional"))
    )
    (net (code "56") (name "SS{slash}PIN10") (class "Default")
      (node (ref "JP3") (pin "D10") (pinfunction "*D10_D10") (pintype "bidirectional"))
      (node (ref "JP6") (pin "1") (pinfunction "1_1") (pintype "passive"))
      (node (ref "U4") (pin "14") (pinfunction "PB2(SS/OC1B)_14") (pintype "bidirectional"))
    )
    (net (code "57") (name "TX") (class "Default")
      (node (ref "JP3") (pin "D1") (pinfunction "D1_D1") (pintype "bidirectional"))
      (node (ref "JP7") (pin "1") (pinfunction "1_1") (pintype "passive"))
      (node (ref "R6") (pin "2") (pinfunction "2_2") (pintype "passive"))
      (node (ref "U4") (pin "31") (pinfunction "PD1(TXD)_31") (pintype "bidirectional"))
    )
    (net (code "58") (name "USB_5V") (class "Default")
      (node (ref "C2") (pin "2") (pinfunction "2_2") (pintype "passive"))
      (node (ref "C3") (pin "A") (pinfunction "+_A") (pintype "passive"))
      (node (ref "F2") (pin "2") (pinfunction "2_2") (pintype "passive"))
      (node (ref "Q4") (pin "3") (pinfunction "D_3") (pintype "passive"))
      (node (ref "U1") (pin "15") (pinfunction "VCC_15") (pintype "bidirectional"))
    )
    (net (code "59") (name "VDD5") (class "Default")
      (node (ref "L2") (pin "2") (pinfunction "2_2") (pintype "passive"))
      (node (ref "Q5") (pin "3") (pinfunction "D_3") (pintype "passive"))
    )
    (net (code "60") (name "VIN") (class "Default")
      (node (ref "C10") (pin "2") (pinfunction "2_2") (pintype "passive"))
      (node (ref "C9") (pin "+") (pinfunction "+_+") (pintype "passive"))
      (node (ref "D1") (pin "C") (pinfunction "C_C") (pintype "passive"))
      (node (ref "JP3") (pin "VIN") (pinfunction "VIN_VIN") (pintype "bidirectional"))
      (node (ref "R11") (pin "2") (pinfunction "2_2") (pintype "passive"))
      (node (ref "R18") (pin "1") (pinfunction "1_1") (pintype "passive"))
      (node (ref "U$1") (pin "2") (pinfunction "IN_2") (pintype "bidirectional"))
    )
    (net (code "61") (name "unconnected-(JP4-ID-PadID1)") (class "Default")
      (node (ref "JP4") (pin "ID1") (pinfunction "ID_ID1") (pintype "bidirectional"))
    )
    (net (code "62") (name "unconnected-(S1-S-Pad3)") (class "Default")
      (node (ref "S1") (pin "3") (pinfunction "S_3") (pintype "passive"))
    )
    (net (code "63") (name "unconnected-(U1-CBUS0-Pad18)") (class "Default")
      (node (ref "U1") (pin "18") (pinfunction "CBUS0_18") (pintype "bidirectional"))
    )
    (net (code "64") (name "unconnected-(U1-CBUS3-Pad19)") (class "Default")
      (node (ref "U1") (pin "19") (pinfunction "CBUS3_19") (pintype "bidirectional"))
    )
    (net (code "65") (name "unconnected-(U1-~{CTS}-Pad9)") (class "Default")
      (node (ref "U1") (pin "9") (pinfunction "~{CTS}_9") (pintype "bidirectional"))
    )
    (net (code "66") (name "unconnected-(U1-~{DCD}-Pad8)") (class "Default")
      (node (ref "U1") (pin "8") (pinfunction "~{DCD}_8") (pintype "bidirectional"))
    )
    (net (code "67") (name "unconnected-(U1-~{DSR}-Pad7)") (class "Default")
      (node (ref "U1") (pin "7") (pinfunction "~{DSR}_7") (pintype "bidirectional"))
    )
    (net (code "68") (name "unconnected-(U1-~{RI}-Pad5)") (class "Default")
      (node (ref "U1") (pin "5") (pinfunction "~{RI}_5") (pintype "bidirectional"))
    )
    (net (code "69") (name "unconnected-(U1-~{RTS}-Pad2)") (class "Default")
      (node (ref "U1") (pin "2") (pinfunction "~{RTS}_2") (pintype "bidirectional"))
    )
  )
)
